# esp8266mosfet.net
KiCad netlist of a schematic drawn in EAGLE
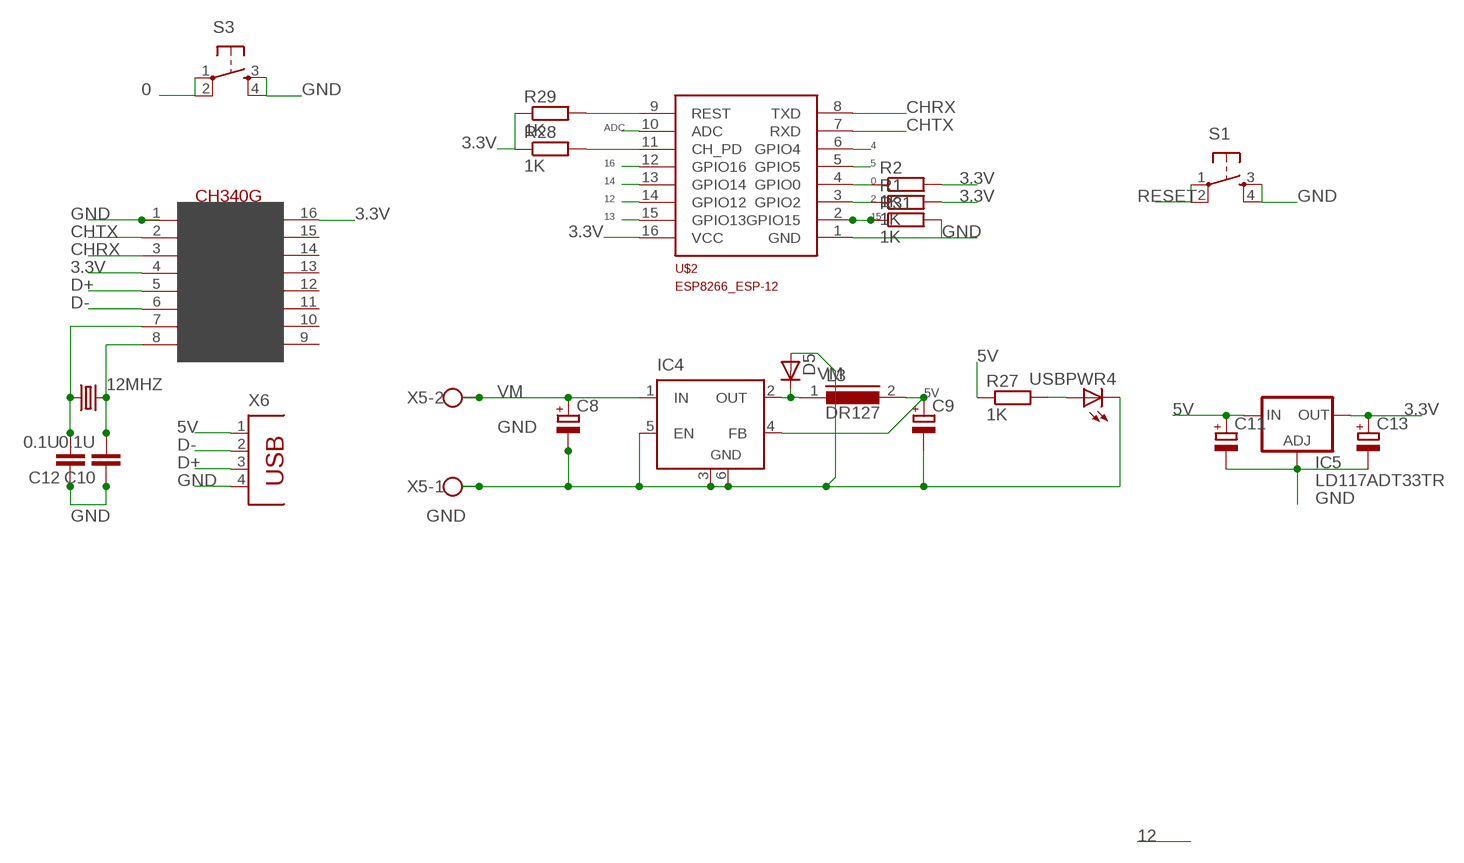
[diagram p0: schematic, sheet 1]

(export (version "E")
  (design (tool "Eeschema 10.0.6"))
  (components
    (comp (ref "12MHZ")
      (value "CRYSTALHC49UP")
      (footprint "eagle-import:HC49UP")
      (libsource (lib "eagle-import") (part "CRYSTALHC49UP"))
    )
    (comp (ref "C8")
      (value "CPOL-EUE")
      (footprint "eagle-import:PANASONIC_E")
      (libsource (lib "eagle-import") (part "resistor_CPOL-EUE"))
    )
    (comp (ref "C9")
      (value "CPOL-EUE")
      (footprint "eagle-import:PANASONIC_E")
      (libsource (lib "eagle-import") (part "resistor_CPOL-EUE"))
    )
    (comp (ref "C10")
      (value "0.1U")
      (footprint "eagle-import:C1206")
      (libsource (lib "eagle-import") (part "C-EUC1206"))
    )
    (comp (ref "C11")
      (value "CPOL-EUC")
      (footprint "eagle-import:PANASONIC_C")
      (libsource (lib "eagle-import") (part "CPOL-EUC"))
    )
    (comp (ref "C12")
      (value "0.1U")
      (footprint "eagle-import:C1206")
      (libsource (lib "eagle-import") (part "C-EUC1206"))
    )
    (comp (ref "C13")
      (value "CPOL-EUC")
      (footprint "eagle-import:PANASONIC_C")
      (libsource (lib "eagle-import") (part "CPOL-EUC"))
    )
    (comp (ref "D5")
      (value "D-SOD-87")
      (footprint "eagle-import:SOD87")
      (libsource (lib "eagle-import") (part "D-SOD-87"))
    )
    (comp (ref "IC4")
      (value "LM2596S")
      (footprint "eagle-import:TO263-5")
      (libsource (lib "eagle-import") (part "LM2596S"))
    )
    (comp (ref "IC5")
      (value "LD117ADT33TR")
      (footprint "eagle-import:DPACK")
      (libsource (lib "eagle-import") (part "LD117A?DT33TR"))
    )
    (comp (ref "L3")
      (value "DR127")
      (footprint "eagle-import:DR127")
      (libsource (lib "eagle-import") (part "DR127"))
    )
    (comp (ref "R1")
      (value "1K")
      (footprint "eagle-import:M1206")
      (libsource (lib "eagle-import") (part "R-EU_M1206"))
    )
    (comp (ref "R2")
      (value "1K")
      (footprint "eagle-import:M1206")
      (libsource (lib "eagle-import") (part "R-EU_M1206"))
    )
    (comp (ref "R27")
      (value "1K")
      (footprint "eagle-import:M1206")
      (libsource (lib "eagle-import") (part "R-EU_M1206"))
    )
    (comp (ref "R28")
      (value "1K")
      (footprint "eagle-import:M1206")
      (libsource (lib "eagle-import") (part "R-EU_M1206"))
    )
    (comp (ref "R29")
      (value "1K")
      (footprint "eagle-import:M1206")
      (libsource (lib "eagle-import") (part "R-EU_M1206"))
    )
    (comp (ref "R31")
      (value "1K")
      (footprint "eagle-import:M1206")
      (libsource (lib "eagle-import") (part "R-EU_M1206"))
    )
    (comp (ref "S1")
      (value "TAC_SWITCHPTH")
      (footprint "eagle-import:TACTILE-PTH")
      (libsource (lib "eagle-import") (part "TAC_SWITCHPTH"))
    )
    (comp (ref "S3")
      (value "TAC_SWITCHPTH")
      (footprint "eagle-import:TACTILE-PTH")
      (libsource (lib "eagle-import") (part "TAC_SWITCHPTH"))
    )
    (comp (ref "U$2")
      (value "ESP8266_ESP-12")
      (footprint "eagle-import:ESP8266-ESP12")
      (libsource (lib "eagle-import") (part "ESP8266_ESP-12"))
    )
    (comp (ref "U$4")
      (value "CH340G")
      (footprint "eagle-import:SOIC16")
      (libsource (lib "eagle-import") (part "CH340G"))
    )
    (comp (ref "USBPWR4")
      (value "LED3MM")
      (footprint "eagle-import:LED3MM")
      (libsource (lib "eagle-import") (part "LED3MM"))
    )
    (comp (ref "X5")
      (value "W237-102")
      (footprint "eagle-import:W237-102")
      (fields (field (name "MPN") "237-102"))
      (libsource (lib "eagle-import") (part "W237-102"))
    )
    (comp (ref "X6")
      (value "PN61729")
      (footprint "eagle-import:PN61729")
      (libsource (lib "eagle-import") (part "PN61729"))
    )
  )
  (nets
    (net (code "1") (name "/0") (class "Default")
      (node (ref "R2") (pin "1") (pinfunction "1_1") (pintype "passive"))
      (node (ref "S3") (pin "1") (pinfunction "1_1") (pintype "passive"))
      (node (ref "S3") (pin "2") (pinfunction "2_2") (pintype "passive"))
      (node (ref "U$2") (pin "4") (pinfunction "GPIO0_4") (pintype "bidirectional"))
    )
    (net (code "2") (name "/2") (class "Default")
      (node (ref "R1") (pin "1") (pinfunction "1_1") (pintype "passive"))
      (node (ref "U$2") (pin "3") (pinfunction "GPIO2_3") (pintype "bidirectional"))
    )
    (net (code "3") (name "/3.3V") (class "Default")
      (node (ref "C13") (pin "+") (pinfunction "+_+") (pintype "passive"))
      (node (ref "IC5") (pin "4") (pinfunction "OUT_4") (pintype "passive"))
      (node (ref "R1") (pin "2") (pinfunction "2_2") (pintype "passive"))
      (node (ref "R2") (pin "2") (pinfunction "2_2") (pintype "passive"))
      (node (ref "R28") (pin "1") (pinfunction "1_1") (pintype "passive"))
      (node (ref "R29") (pin "1") (pinfunction "1_1") (pintype "passive"))
      (node (ref "U$2") (pin "16") (pinfunction "VCC_16") (pintype "bidirectional"))
      (node (ref "U$4") (pin "16") (pinfunction "VCC_16") (pintype "bidirectional"))
      (node (ref "U$4") (pin "4") (pinfunction "V3_4") (pintype "bidirectional"))
    )
    (net (code "4") (name "/4") (class "Default")
      (node (ref "U$2") (pin "6") (pinfunction "GPIO4_6") (pintype "bidirectional"))
    )
    (net (code "5") (name "/5") (class "Default")
      (node (ref "U$2") (pin "5") (pinfunction "GPIO5_5") (pintype "bidirectional"))
    )
    (net (code "6") (name "/5V") (class "Default")
      (node (ref "C11") (pin "+") (pinfunction "+_+") (pintype "passive"))
      (node (ref "C9") (pin "+") (pinfunction "+_+") (pintype "passive"))
      (node (ref "IC4") (pin "4") (pinfunction "FB_4") (pintype "input"))
      (node (ref "IC5") (pin "3") (pinfunction "IN_3") (pintype "input"))
      (node (ref "L3") (pin "2") (pinfunction "2_2") (pintype "passive"))
      (node (ref "R27") (pin "1") (pinfunction "1_1") (pintype "passive"))
      (node (ref "X6") (pin "1") (pinfunction "1_1") (pintype "passive"))
    )
    (net (code "7") (name "/12") (class "Default")
      (node (ref "U$2") (pin "14") (pinfunction "GPIO12_14") (pintype "bidirectional"))
    )
    (net (code "8") (name "/13") (class "Default")
      (node (ref "U$2") (pin "15") (pinfunction "GPIO13_15") (pintype "bidirectional"))
    )
    (net (code "9") (name "/14") (class "Default")
      (node (ref "U$2") (pin "13") (pinfunction "GPIO14_13") (pintype "bidirectional"))
    )
    (net (code "10") (name "/15") (class "Default")
      (node (ref "R31") (pin "1") (pinfunction "1_1") (pintype "passive"))
      (node (ref "U$2") (pin "2") (pinfunction "GPIO15_2") (pintype "bidirectional"))
    )
    (net (code "11") (name "/16") (class "Default")
      (node (ref "U$2") (pin "12") (pinfunction "GPIO16_12") (pintype "bidirectional"))
    )
    (net (code "12") (name "/ADC") (class "Default")
      (node (ref "U$2") (pin "10") (pinfunction "ADC_10") (pintype "bidirectional"))
    )
    (net (code "13") (name "/CHRX") (class "Default")
      (node (ref "U$2") (pin "8") (pinfunction "TXD_8") (pintype "bidirectional"))
      (node (ref "U$4") (pin "3") (pinfunction "RX_3") (pintype "bidirectional"))
    )
    (net (code "14") (name "/CHTX") (class "Default")
      (node (ref "U$2") (pin "7") (pinfunction "RXD_7") (pintype "bidirectional"))
      (node (ref "U$4") (pin "2") (pinfunction "TX_2") (pintype "bidirectional"))
    )
    (net (code "15") (name "/D+") (class "Default")
      (node (ref "U$4") (pin "5") (pinfunction "D+_5") (pintype "bidirectional"))
      (node (ref "X6") (pin "3") (pinfunction "3_3") (pintype "passive"))
    )
    (net (code "16") (name "/D-") (class "Default")
      (node (ref "U$4") (pin "6") (pinfunction "D-_6") (pintype "bidirectional"))
      (node (ref "X6") (pin "2") (pinfunction "2_2") (pintype "passive"))
    )
    (net (code "17") (name "/GND") (class "Default")
      (node (ref "C10") (pin "1") (pinfunction "1_1") (pintype "passive"))
      (node (ref "C11") (pin "-") (pinfunction "-_-") (pintype "passive"))
      (node (ref "C12") (pin "1") (pinfunction "1_1") (pintype "passive"))
      (node (ref "C13") (pin "-") (pinfunction "-_-") (pintype "passive"))
      (node (ref "C8") (pin "-") (pinfunction "-_-") (pintype "passive"))
      (node (ref "C9") (pin "-") (pinfunction "-_-") (pintype "passive"))
      (node (ref "D5") (pin "2") (pinfunction "A_2") (pintype "passive"))
      (node (ref "IC4") (pin "3") (pinfunction "GND_3") (pintype "power_in"))
      (node (ref "IC4") (pin "5") (pinfunction "EN_5") (pintype "input"))
      (node (ref "IC4") (pin "6") (pinfunction "GND_6") (pintype "power_in"))
      (node (ref "IC5") (pin "1") (pinfunction "ADJ_1") (pintype "input"))
      (node (ref "R31") (pin "2") (pinfunction "2_2") (pintype "passive"))
      (node (ref "S1") (pin "3") (pinfunction "3_3") (pintype "passive"))
      (node (ref "S1") (pin "4") (pinfunction "4_4") (pintype "passive"))
      (node (ref "S3") (pin "3") (pinfunction "3_3") (pintype "passive"))
      (node (ref "S3") (pin "4") (pinfunction "4_4") (pintype "passive"))
      (node (ref "U$2") (pin "1") (pinfunction "GND_1") (pintype "bidirectional"))
      (node (ref "U$4") (pin "1") (pinfunction "GND_1") (pintype "bidirectional"))
      (node (ref "USBPWR4") (pin "K") (pinfunction "C_K") (pintype "passive"))
      (node (ref "X5") (pin "1") (pinfunction "KL_1") (pintype "passive"))
      (node (ref "X6") (pin "4") (pinfunction "4_4") (pintype "passive"))
    )
    (net (code "18") (name "/RESET") (class "Default")
      (node (ref "R29") (pin "2") (pinfunction "2_2") (pintype "passive"))
      (node (ref "S1") (pin "1") (pinfunction "1_1") (pintype "passive"))
      (node (ref "S1") (pin "2") (pinfunction "2_2") (pintype "passive"))
      (node (ref "U$2") (pin "9") (pinfunction "REST_9") (pintype "bidirectional"))
    )
    (net (code "19") (name "/VM") (class "Default")
      (node (ref "C8") (pin "+") (pinfunction "+_+") (pintype "passive"))
      (node (ref "IC4") (pin "1") (pinfunction "IN_1") (pintype "input"))
      (node (ref "X5") (pin "2") (pinfunction "KL_2") (pintype "passive"))
    )
    (net (code "20") (name "Net-(D5-C)") (class "Default")
      (node (ref "D5") (pin "1") (pinfunction "C_1") (pintype "passive"))
      (node (ref "IC4") (pin "2") (pinfunction "OUT_2") (pintype "output"))
      (node (ref "L3") (pin "1") (pinfunction "1_1") (pintype "passive"))
    )
    (net (code "21") (name "Net-(R27-Pad2)") (class "Default")
      (node (ref "R27") (pin "2") (pinfunction "2_2") (pintype "passive"))
      (node (ref "USBPWR4") (pin "A") (pinfunction "A_A") (pintype "passive"))
    )
    (net (code "22") (name "Net-(U$2-CH_PD)") (class "Default")
      (node (ref "R28") (pin "2") (pinfunction "2_2") (pintype "passive"))
      (node (ref "U$2") (pin "11") (pinfunction "CH_PD_11") (pintype "bidirectional"))
    )
    (net (code "23") (name "Net-(U$4-XI)") (class "Default")
      (node (ref "12MHZ") (pin "1") (pinfunction "1_1") (pintype "passive"))
      (node (ref "C12") (pin "2") (pinfunction "2_2") (pintype "passive"))
      (node (ref "U$4") (pin "7") (pinfunction "XI_7") (pintype "bidirectional"))
    )
    (net (code "24") (name "Net-(U$4-XO)") (class "Default")
      (node (ref "12MHZ") (pin "2") (pinfunction "2_2") (pintype "passive"))
      (node (ref "C10") (pin "2") (pinfunction "2_2") (pintype "passive"))
      (node (ref "U$4") (pin "8") (pinfunction "XO_8") (pintype "bidirectional"))
    )
    (net (code "25") (name "unconnected-(U$4-CTS-Pad9)") (class "Default")
      (node (ref "U$4") (pin "9") (pinfunction "CTS_9") (pintype "bidirectional"))
    )
    (net (code "26") (name "unconnected-(U$4-DCD-Pad12)") (class "Default")
      (node (ref "U$4") (pin "12") (pinfunction "DCD_12") (pintype "bidirectional"))
    )
    (net (code "27") (name "unconnected-(U$4-DSR-Pad10)") (class "Default")
      (node (ref "U$4") (pin "10") (pinfunction "DSR_10") (pintype "bidirectional"))
    )
    (net (code "28") (name "unconnected-(U$4-DTR-Pad13)") (class "Default")
      (node (ref "U$4") (pin "13") (pinfunction "DTR_13") (pintype "bidirectional"))
    )
    (net (code "29") (name "unconnected-(U$4-RI-Pad11)") (class "Default")
      (node (ref "U$4") (pin "11") (pinfunction "RI_11") (pintype "bidirectional"))
    )
    (net (code "30") (name "unconnected-(U$4-RS232-Pad15)") (class "Default")
      (node (ref "U$4") (pin "15") (pinfunction "RS232_15") (pintype "bidirectional"))
    )
    (net (code "31") (name "unconnected-(U$4-RTS-Pad14)") (class "Default")
      (node (ref "U$4") (pin "14") (pinfunction "RTS_14") (pintype "bidirectional"))
    )
  )
)
